# ProPrj_E73__2025-03-02.net
KiCad netlist of a schematic drawn in EasyEDA Pro
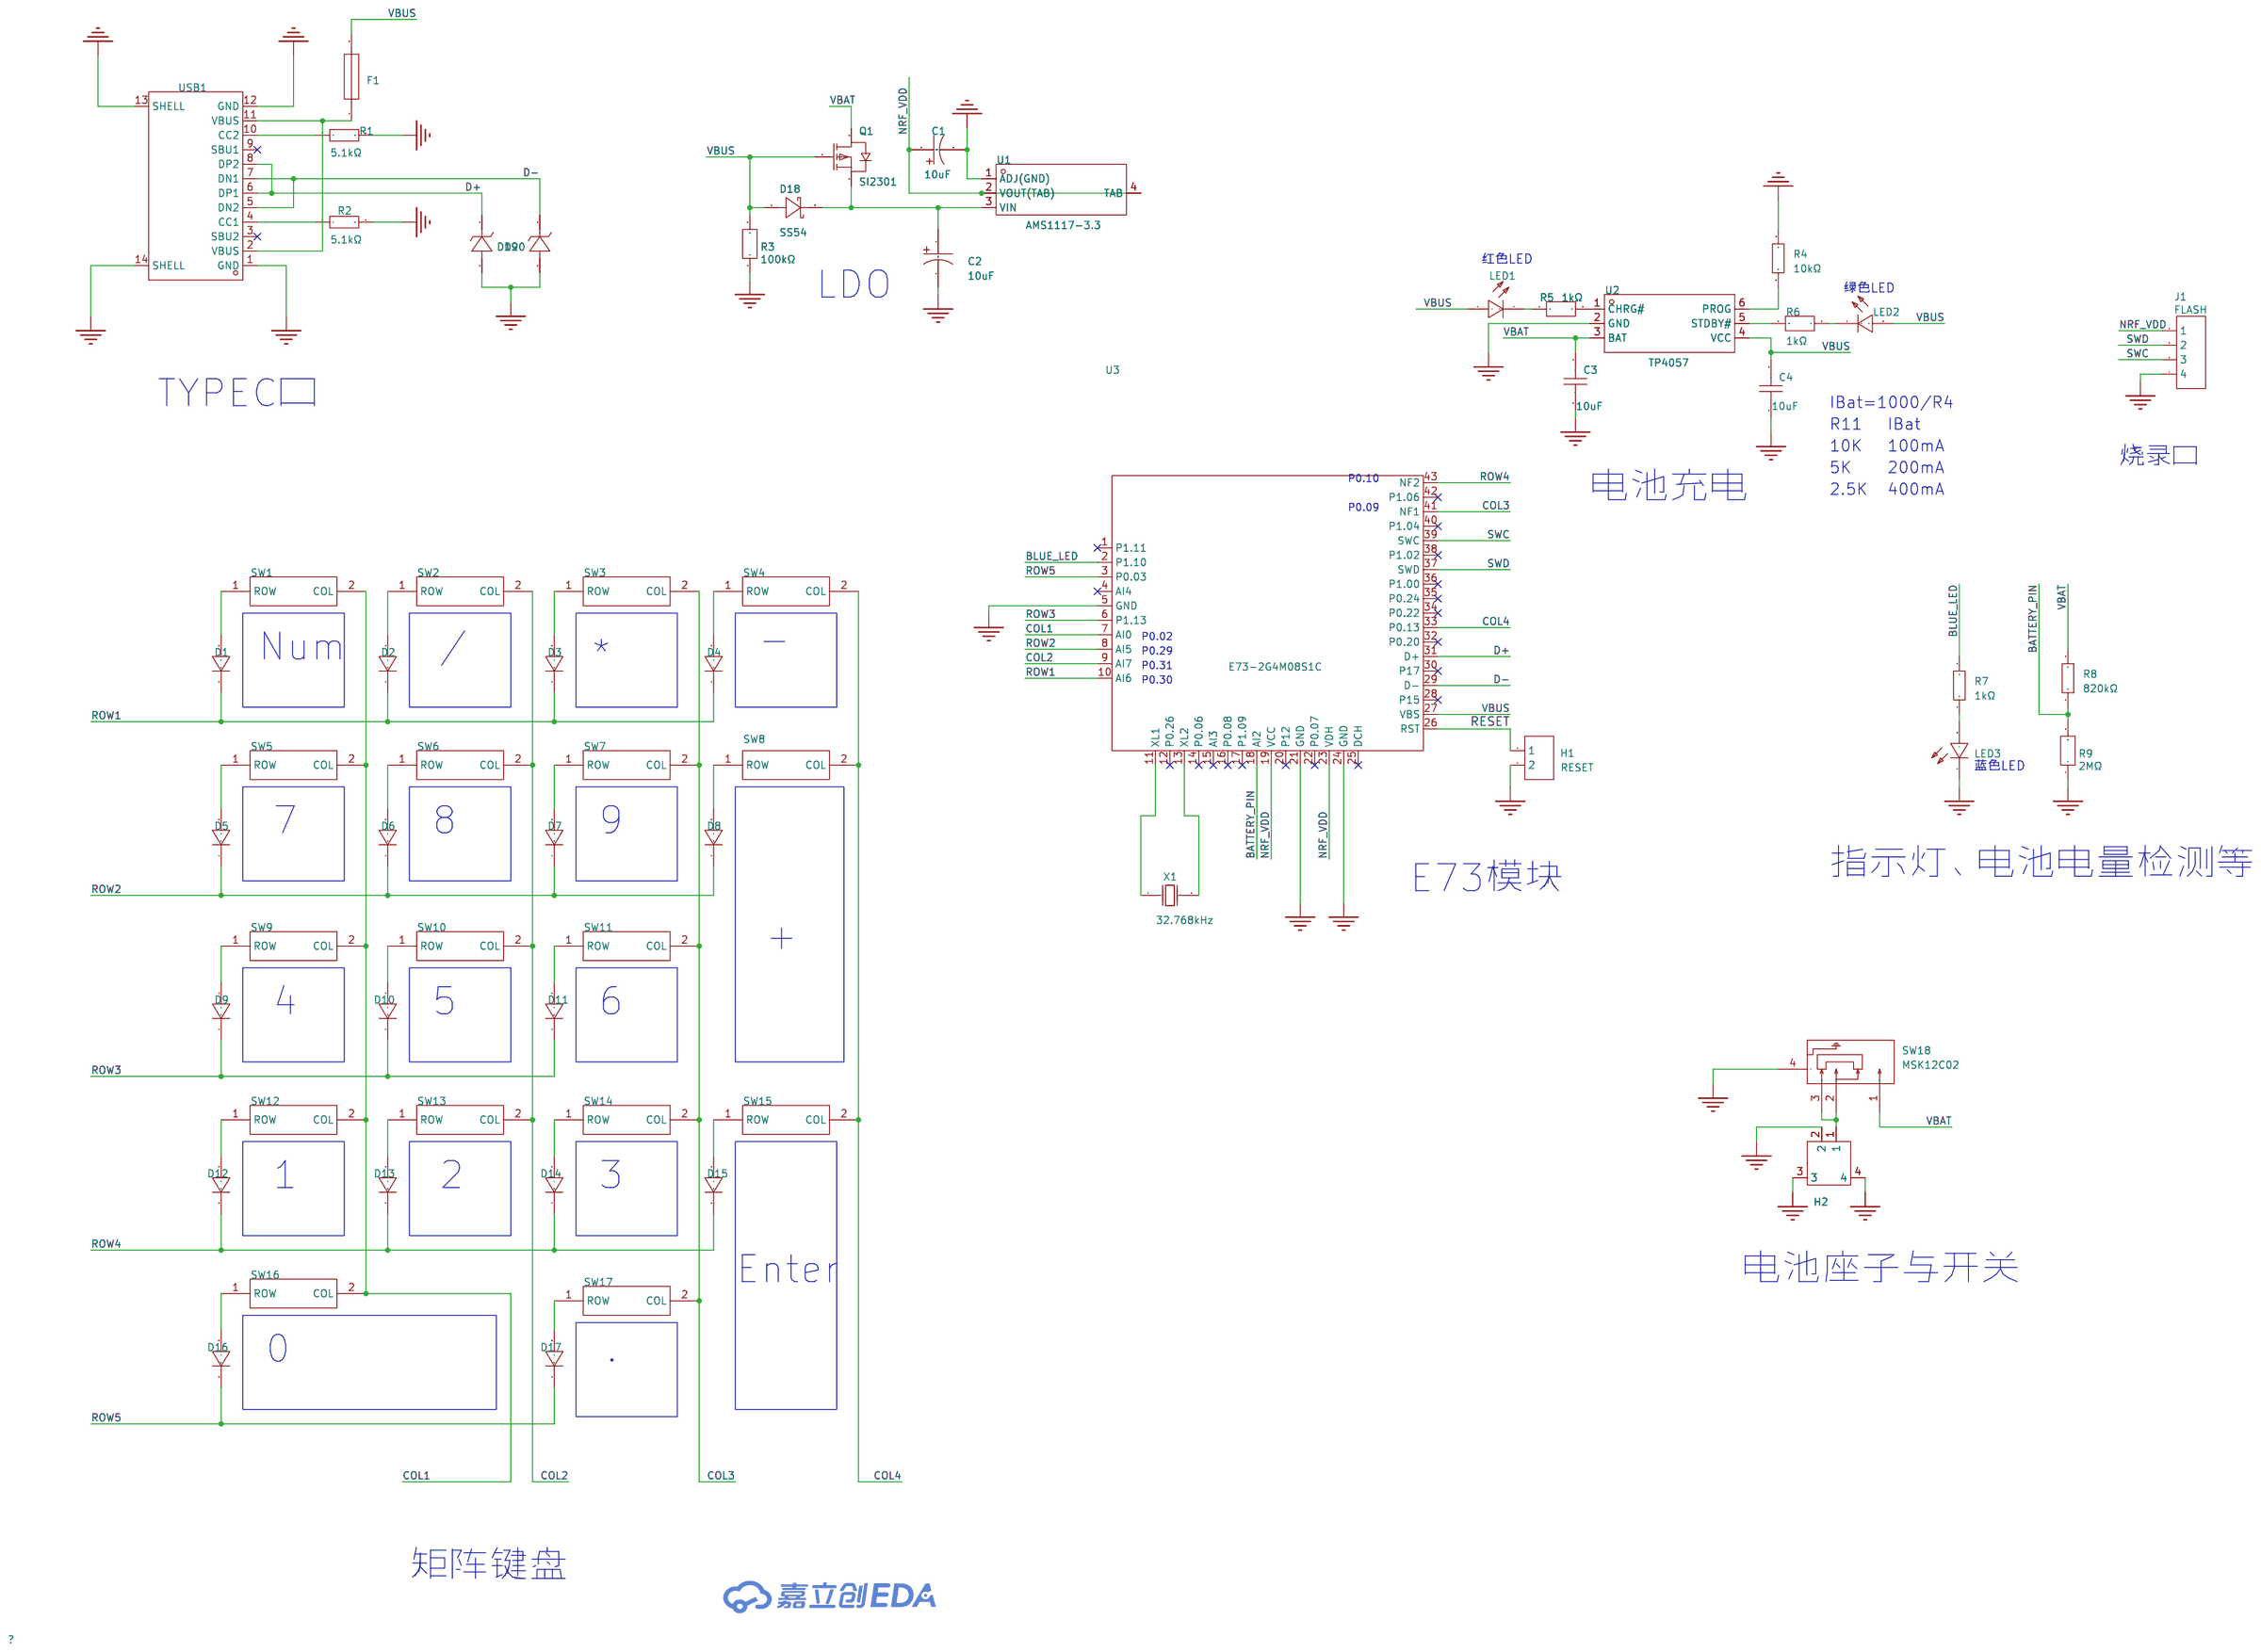
[diagram p0: schematic sheet]

(export (version "E")
  (design (tool "Eeschema 10.0.6"))
  (components
    (comp (ref "C1")
      (value "10uF")
      (footprint "easyedapro:CAP-SMD_L3.2-W1.6")
      (description "容值:10uF;精度:±10%;额定电压:16V;等效串联电阻:2Ω@100kHz;")
      (fields
        (field (name "Manufacturer Part") "CA45-A-16V-10μF-K")
        (field (name "Manufacturer") "TORCH(火炬)")
      )
      (libsource (lib "easyedapro") (part "CA45-A-16V-10μF-K"))
    )
    (comp (ref "C2")
      (value "10uF")
      (footprint "easyedapro:CAP-SMD_L3.2-W1.6")
      (description "容值:10uF;精度:±10%;额定电压:16V;等效串联电阻:2Ω@100kHz;")
      (fields
        (field (name "Manufacturer Part") "CA45-A-16V-10μF-K")
        (field (name "Manufacturer") "TORCH(火炬)")
      )
      (libsource (lib "easyedapro") (part "CA45-A-16V-10μF-K"))
    )
    (comp (ref "C3")
      (value "10uF")
      (footprint "easyedapro:C0603")
      (description "容值:10uF;精度:±20%;额定电压:16V;材质(温度系数):X5R;")
      (fields
        (field (name "Manufacturer Part") "HGC0603R5106M160NTHJ")
        (field (name "Manufacturer") "Chinocera(华瓷)")
      )
      (libsource (lib "easyedapro") (part "HGC0603R5106M160NTHJ"))
    )
    (comp (ref "C4")
      (value "10uF")
      (footprint "easyedapro:C0603")
      (description "容值:10uF;精度:±20%;额定电压:16V;材质(温度系数):X5R;")
      (fields
        (field (name "Manufacturer Part") "HGC0603R5106M160NTHJ")
        (field (name "Manufacturer") "Chinocera(华瓷)")
      )
      (libsource (lib "easyedapro") (part "HGC0603R5106M160NTHJ"))
    )
    (comp (ref "D1")
      (value "LL4148")
      (footprint "easyedapro:LL-34_L3.5-W1.5-RD")
      (description "二极管配置:-;正向压降(Vf):1V@10mA;直流反向耐压(Vr):75V;整流电流:200mA;反向恢复时间(trr):4ns;")
      (fields (field (name "Manufacturer") "MDD(辰达半导体)"))
      (libsource (lib "easyedapro") (part "LL4148_C435829"))
    )
    (comp (ref "D2")
      (value "LL4148")
      (footprint "easyedapro:LL-34_L3.5-W1.5-RD")
      (description "二极管配置:-;正向压降(Vf):1V@10mA;直流反向耐压(Vr):75V;整流电流:200mA;反向恢复时间(trr):4ns;")
      (fields (field (name "Manufacturer") "MDD(辰达半导体)"))
      (libsource (lib "easyedapro") (part "LL4148_C435829"))
    )
    (comp (ref "D3")
      (value "LL4148")
      (footprint "easyedapro:LL-34_L3.5-W1.5-RD")
      (description "二极管配置:-;正向压降(Vf):1V@10mA;直流反向耐压(Vr):75V;整流电流:200mA;反向恢复时间(trr):4ns;")
      (fields (field (name "Manufacturer") "MDD(辰达半导体)"))
      (libsource (lib "easyedapro") (part "LL4148_C435829"))
    )
    (comp (ref "D4")
      (value "LL4148")
      (footprint "easyedapro:LL-34_L3.5-W1.5-RD")
      (description "二极管配置:-;正向压降(Vf):1V@10mA;直流反向耐压(Vr):75V;整流电流:200mA;反向恢复时间(trr):4ns;")
      (fields (field (name "Manufacturer") "MDD(辰达半导体)"))
      (libsource (lib "easyedapro") (part "LL4148_C435829"))
    )
    (comp (ref "D5")
      (value "LL4148")
      (footprint "easyedapro:LL-34_L3.5-W1.5-RD")
      (description "二极管配置:-;正向压降(Vf):1V@10mA;直流反向耐压(Vr):75V;整流电流:200mA;反向恢复时间(trr):4ns;")
      (fields (field (name "Manufacturer") "MDD(辰达半导体)"))
      (libsource (lib "easyedapro") (part "LL4148_C435829"))
    )
    (comp (ref "D6")
      (value "LL4148")
      (footprint "easyedapro:LL-34_L3.5-W1.5-RD")
      (description "二极管配置:-;正向压降(Vf):1V@10mA;直流反向耐压(Vr):75V;整流电流:200mA;反向恢复时间(trr):4ns;")
      (fields (field (name "Manufacturer") "MDD(辰达半导体)"))
      (libsource (lib "easyedapro") (part "LL4148_C435829"))
    )
    (comp (ref "D7")
      (value "LL4148")
      (footprint "easyedapro:LL-34_L3.5-W1.5-RD")
      (description "二极管配置:-;正向压降(Vf):1V@10mA;直流反向耐压(Vr):75V;整流电流:200mA;反向恢复时间(trr):4ns;")
      (fields (field (name "Manufacturer") "MDD(辰达半导体)"))
      (libsource (lib "easyedapro") (part "LL4148_C435829"))
    )
    (comp (ref "D8")
      (value "LL4148")
      (footprint "easyedapro:LL-34_L3.5-W1.5-RD")
      (description "二极管配置:-;正向压降(Vf):1V@10mA;直流反向耐压(Vr):75V;整流电流:200mA;反向恢复时间(trr):4ns;")
      (fields (field (name "Manufacturer") "MDD(辰达半导体)"))
      (libsource (lib "easyedapro") (part "LL4148_C435829"))
    )
    (comp (ref "D9")
      (value "LL4148")
      (footprint "easyedapro:LL-34_L3.5-W1.5-RD")
      (description "二极管配置:-;正向压降(Vf):1V@10mA;直流反向耐压(Vr):75V;整流电流:200mA;反向恢复时间(trr):4ns;")
      (fields (field (name "Manufacturer") "MDD(辰达半导体)"))
      (libsource (lib "easyedapro") (part "LL4148_C435829"))
    )
    (comp (ref "D10")
      (value "LL4148")
      (footprint "easyedapro:LL-34_L3.5-W1.5-RD")
      (description "二极管配置:-;正向压降(Vf):1V@10mA;直流反向耐压(Vr):75V;整流电流:200mA;反向恢复时间(trr):4ns;")
      (fields (field (name "Manufacturer") "MDD(辰达半导体)"))
      (libsource (lib "easyedapro") (part "LL4148_C435829"))
    )
    (comp (ref "D11")
      (value "LL4148")
      (footprint "easyedapro:LL-34_L3.5-W1.5-RD")
      (description "二极管配置:-;正向压降(Vf):1V@10mA;直流反向耐压(Vr):75V;整流电流:200mA;反向恢复时间(trr):4ns;")
      (fields (field (name "Manufacturer") "MDD(辰达半导体)"))
      (libsource (lib "easyedapro") (part "LL4148_C435829"))
    )
    (comp (ref "D12")
      (value "LL4148")
      (footprint "easyedapro:LL-34_L3.5-W1.5-RD")
      (description "二极管配置:-;正向压降(Vf):1V@10mA;直流反向耐压(Vr):75V;整流电流:200mA;反向恢复时间(trr):4ns;")
      (fields (field (name "Manufacturer") "MDD(辰达半导体)"))
      (libsource (lib "easyedapro") (part "LL4148_C435829"))
    )
    (comp (ref "D13")
      (value "LL4148")
      (footprint "easyedapro:LL-34_L3.5-W1.5-RD")
      (description "二极管配置:-;正向压降(Vf):1V@10mA;直流反向耐压(Vr):75V;整流电流:200mA;反向恢复时间(trr):4ns;")
      (fields (field (name "Manufacturer") "MDD(辰达半导体)"))
      (libsource (lib "easyedapro") (part "LL4148_C435829"))
    )
    (comp (ref "D14")
      (value "LL4148")
      (footprint "easyedapro:LL-34_L3.5-W1.5-RD")
      (description "二极管配置:-;正向压降(Vf):1V@10mA;直流反向耐压(Vr):75V;整流电流:200mA;反向恢复时间(trr):4ns;")
      (fields (field (name "Manufacturer") "MDD(辰达半导体)"))
      (libsource (lib "easyedapro") (part "LL4148_C435829"))
    )
    (comp (ref "D15")
      (value "LL4148")
      (footprint "easyedapro:LL-34_L3.5-W1.5-RD")
      (description "二极管配置:-;正向压降(Vf):1V@10mA;直流反向耐压(Vr):75V;整流电流:200mA;反向恢复时间(trr):4ns;")
      (fields (field (name "Manufacturer") "MDD(辰达半导体)"))
      (libsource (lib "easyedapro") (part "LL4148_C435829"))
    )
    (comp (ref "D16")
      (value "LL4148")
      (footprint "easyedapro:LL-34_L3.5-W1.5-RD")
      (description "二极管配置:-;正向压降(Vf):1V@10mA;直流反向耐压(Vr):75V;整流电流:200mA;反向恢复时间(trr):4ns;")
      (fields (field (name "Manufacturer") "MDD(辰达半导体)"))
      (libsource (lib "easyedapro") (part "LL4148_C435829"))
    )
    (comp (ref "D17")
      (value "LL4148")
      (footprint "easyedapro:LL-34_L3.5-W1.5-RD")
      (description "二极管配置:-;正向压降(Vf):1V@10mA;直流反向耐压(Vr):75V;整流电流:200mA;反向恢复时间(trr):4ns;")
      (fields (field (name "Manufacturer") "MDD(辰达半导体)"))
      (libsource (lib "easyedapro") (part "LL4148_C435829"))
    )
    (comp (ref "D18")
      (value "SS54")
      (footprint "easyedapro:SMA_L4.3-W2.6-LS5.0-FD")
      (description "二极管配置:独立式;正向压降(Vf):550mV@5.0A;直流反向耐压(Vr):40V;整流电流:5A;")
      (fields (field (name "Manufacturer") "宏迦橙"))
      (libsource (lib "easyedapro") (part "SS54_C7420369"))
    )
    (comp (ref "D19")
      (value "BZT52C3V6S")
      (footprint "easyedapro:SOD-323_L1.7-W1.3-LS2.6-RD")
      (description "二极管配置:独立式;稳压值(标称值):3.6V;稳压值(范围):3.4V~3.8V;功率(Pd):200mW;")
      (fields (field (name "Manufacturer") "宏迦橙"))
      (libsource (lib "easyedapro") (part "BZT52C3V6S_C19077438"))
    )
    (comp (ref "D20")
      (value "BZT52C3V6S")
      (footprint "easyedapro:SOD-323_L1.7-W1.3-LS2.6-RD")
      (description "二极管配置:独立式;稳压值(标称值):3.6V;稳压值(范围):3.4V~3.8V;功率(Pd):200mW;")
      (fields (field (name "Manufacturer") "宏迦橙"))
      (libsource (lib "easyedapro") (part "BZT52C3V6S_C19077438"))
    )
    (comp (ref "F1")
      (value "JK-nSMD050-30")
      (footprint "easyedapro:F1206")
      (description "最大电压:30V;最大电流:100A;保持电流:500mA;跳闸电流:1A;")
      (fields (field (name "Manufacturer") "JK(金科)"))
      (libsource (lib "easyedapro") (part "JK-NSMD050-30V"))
    )
    (comp (ref "H1")
      (value "RESET")
      (footprint "easyedapro:PIN02")
      (libsource (lib "easyedapro") (part "RESET"))
    )
    (comp (ref "H2") (value "2.54-2P WT") (libsource (lib "easyedapro") (part "Battery")))
    (comp (ref "J1")
      (value "FLASH")
      (footprint "easyedapro:PIN04")
      (libsource (lib "easyedapro") (part "FLASH"))
    )
    (comp (ref "LED1")
      (value "NCD0603R1")
      (footprint "easyedapro:LED0603-RD_RED")
      (fields (field (name "Manufacturer") "国星光电"))
      (libsource (lib "easyedapro") (part "FC-DA1608HRK-620D"))
    )
    (comp (ref "LED2")
      (value "NCD0603G1")
      (footprint "easyedapro:LED0603-RD_1")
      (fields (field (name "Manufacturer") "国星光电"))
      (libsource (lib "easyedapro") (part "FC-D1608UGK-520D10"))
    )
    (comp (ref "LED3")
      (value "NCD0603B1")
      (footprint "easyedapro:LED0603-RD")
      (fields (field (name "Manufacturer") "国星光电"))
      (libsource (lib "easyedapro") (part "FC-DA1608BK-470H10"))
    )
    (comp (ref "Q1")
      (value "SI2301")
      (footprint "easyedapro:SOT-23-3_L2.9-W1.3-P1.90-LS2.4-BR")
      (fields (field (name "Manufacturer") "YONGYUTAI(永裕泰)"))
      (libsource (lib "easyedapro") (part "SI2301_C2891731"))
    )
    (comp (ref "R1")
      (value "5.1kΩ")
      (footprint "easyedapro:R0603")
      (description "电阻类型:厚膜电阻;阻值:5.1kΩ;精度:±1%;功率:100mW;最大工作电压:75V;温度系数:±100ppm/°C;")
      (fields
        (field (name "Manufacturer Part") "0603WAF5101T5E")
        (field (name "Manufacturer") "UNI-ROYAL(厚声)")
      )
      (libsource (lib "easyedapro") (part "0603WAF5101T5E"))
    )
    (comp (ref "R2")
      (value "5.1kΩ")
      (footprint "easyedapro:R0603")
      (description "电阻类型:厚膜电阻;阻值:5.1kΩ;精度:±1%;功率:100mW;最大工作电压:75V;温度系数:±100ppm/°C;")
      (fields
        (field (name "Manufacturer Part") "0603WAF5101T5E")
        (field (name "Manufacturer") "UNI-ROYAL(厚声)")
      )
      (libsource (lib "easyedapro") (part "0603WAF5101T5E"))
    )
    (comp (ref "R3")
      (value "100kΩ")
      (fields (field (name "Manufacturer") "UNI-ROYAL(厚声)"))
      (libsource (lib "easyedapro") (part "100K"))
    )
    (comp (ref "R4")
      (value "10kΩ")
      (footprint "easyedapro:R0603")
      (description "电阻类型:厚膜电阻;阻值:10kΩ;精度:±1%;功率:100mW;最大工作电压:75V;温度系数:±100ppm/°C;")
      (fields
        (field (name "Manufacturer Part") "0603WAF1002T5E")
        (field (name "Manufacturer") "UNI-ROYAL(厚声)")
      )
      (libsource (lib "easyedapro") (part "0603WAF1002T5E"))
    )
    (comp (ref "R5")
      (value "1kΩ")
      (fields (field (name "Manufacturer") "UNI-ROYAL(厚声)"))
      (libsource (lib "easyedapro") (part "1K"))
    )
    (comp (ref "R6")
      (value "1kΩ")
      (fields (field (name "Manufacturer") "UNI-ROYAL(厚声)"))
      (libsource (lib "easyedapro") (part "1K"))
    )
    (comp (ref "R7")
      (value "1kΩ")
      (footprint "easyedapro:R0603")
      (description "电阻类型:厚膜电阻;阻值:1kΩ;精度:±1%;功率:100mW;最大工作电压:75V;温度系数:±100ppm/°C;")
      (fields
        (field (name "Manufacturer Part") "0603WAF1001T5E")
        (field (name "Manufacturer") "UNI-ROYAL(厚声)")
      )
      (libsource (lib "easyedapro") (part "0603WAF1001T5E"))
    )
    (comp (ref "R8")
      (value "820kΩ")
      (footprint "easyedapro:R0603")
      (description "电阻类型:厚膜电阻;阻值:820kΩ;精度:±1%;功率:100mW;最大工作电压:75V;温度系数:±100ppm/°C;")
      (fields
        (field (name "Manufacturer Part") "0603WAF8203T5E")
        (field (name "Manufacturer") "UNI-ROYAL(厚声)")
      )
      (libsource (lib "easyedapro") (part "0603WAF8203T5E"))
    )
    (comp (ref "R9")
      (value "2MΩ")
      (fields (field (name "Manufacturer") "UNI-ROYAL(厚声)"))
      (libsource (lib "easyedapro") (part "2M"))
    )
    (comp (ref "SW1")
      (value "~")
      (footprint "easyedapro:键盘轴座(无灯)")
      (libsource (lib "easyedapro") (part "键盘轴座(无灯)"))
    )
    (comp (ref "SW2")
      (value "~")
      (footprint "easyedapro:键盘轴座(无灯)")
      (libsource (lib "easyedapro") (part "键盘轴座(无灯)"))
    )
    (comp (ref "SW3")
      (value "~")
      (footprint "easyedapro:键盘轴座(无灯)")
      (libsource (lib "easyedapro") (part "键盘轴座(无灯)"))
    )
    (comp (ref "SW4")
      (value "~")
      (footprint "easyedapro:键盘轴座(无灯)")
      (libsource (lib "easyedapro") (part "键盘轴座(无灯)"))
    )
    (comp (ref "SW5")
      (value "~")
      (footprint "easyedapro:键盘轴座(无灯)")
      (libsource (lib "easyedapro") (part "键盘轴座(无灯)"))
    )
    (comp (ref "SW6")
      (value "~")
      (footprint "easyedapro:键盘轴座(无灯)")
      (libsource (lib "easyedapro") (part "键盘轴座(无灯)"))
    )
    (comp (ref "SW7")
      (value "~")
      (footprint "easyedapro:键盘轴座(无灯)")
      (libsource (lib "easyedapro") (part "键盘轴座(无灯)"))
    )
    (comp (ref "SW8")
      (value "~")
      (footprint "easyedapro:键盘轴座(无灯)")
      (libsource (lib "easyedapro") (part "键盘轴座(无灯)"))
    )
    (comp (ref "SW9")
      (value "~")
      (footprint "easyedapro:键盘轴座(无灯)")
      (libsource (lib "easyedapro") (part "键盘轴座(无灯)"))
    )
    (comp (ref "SW10")
      (value "~")
      (footprint "easyedapro:键盘轴座(无灯)")
      (libsource (lib "easyedapro") (part "键盘轴座(无灯)"))
    )
    (comp (ref "SW11")
      (value "~")
      (footprint "easyedapro:键盘轴座(无灯)")
      (libsource (lib "easyedapro") (part "键盘轴座(无灯)"))
    )
    (comp (ref "SW12")
      (value "~")
      (footprint "easyedapro:键盘轴座(无灯)")
      (libsource (lib "easyedapro") (part "键盘轴座(无灯)"))
    )
    (comp (ref "SW13")
      (value "~")
      (footprint "easyedapro:键盘轴座(无灯)")
      (libsource (lib "easyedapro") (part "键盘轴座(无灯)"))
    )
    (comp (ref "SW14")
      (value "~")
      (footprint "easyedapro:键盘轴座(无灯)")
      (libsource (lib "easyedapro") (part "键盘轴座(无灯)"))
    )
    (comp (ref "SW15")
      (value "~")
      (footprint "easyedapro:键盘轴座(无灯)")
      (libsource (lib "easyedapro") (part "键盘轴座(无灯)"))
    )
    (comp (ref "SW16")
      (value "~")
      (footprint "easyedapro:键盘轴座(无灯)")
      (libsource (lib "easyedapro") (part "键盘轴座(无灯)"))
    )
    (comp (ref "SW17")
      (value "~")
      (footprint "easyedapro:键盘轴座(无灯)")
      (libsource (lib "easyedapro") (part "键盘轴座(无灯)"))
    )
    (comp (ref "SW18")
      (value "MSK12C02")
      (footprint "easyedapro:SW-TH_MSK12C02")
      (description "电路结构:单刀双掷;安装方式:卧贴;开关颜色:-;额定电流(DC):50mA;额定电压(DC):12V;额定电流(AC):-;额定电压(AC):-;机械寿命:1万次;")
      (fields (field (name "Manufacturer") "SHOU HAN(首韩)"))
      (libsource (lib "easyedapro") (part "MSK12C02"))
    )
    (comp (ref "U1")
      (value "AMS1117-3.3")
      (footprint "easyedapro:SOT-223-4_L6.5-W3.5-P2.30-LS7.0-BR")
      (description "输出类型:固定;工作电压:12V;输出电压:3.3V;输出电流:1A;电源纹波抑制比(PSRR):60dB@(120Hz);输出极性:正极;")
      (fields (field (name "Manufacturer") "UMW(友台半导体)"))
      (libsource (lib "easyedapro") (part "AMS1117-3.3_C347222"))
    )
    (comp (ref "U2")
      (value "TP4057")
      (footprint "easyedapro:SOT-23-6_L2.9-W1.6-P0.95-LS2.8-BR")
      (description "电源电压:6.5V;最大充电电流:500mA;电池类型:锂离子/聚合物;电池节数:1;")
      (fields (field (name "Manufacturer") "UMW(友台半导体)"))
      (libsource (lib "easyedapro") (part "TP4057_C725791"))
    )
    (comp (ref "U3")
      (value "E73-2G4M08S1C")
      (footprint "easyedapro:WIRELM-SMD_E73-2G4M08S1C")
      (fields (field (name "Manufacturer") "EBYTE(亿佰特)"))
      (libsource (lib "easyedapro") (part "E73-2G4M08S1C"))
    )
    (comp (ref "USB1")
      (value "TYPE-C 16PIN 2MD(073)")
      (footprint "easyedapro:USB-C-SMD_TYPE-C-6PIN-2MD-073")
      (description "连接器类型:Type-C;标准:USB 3.1;公母:母;安装方式:卧贴;触点数量:16P;端口数量:1;额定电流 - 电源:5A;工作温度范围:-25°C~+85°C;")
      (fields (field (name "Manufacturer") "SHOU HAN(首韩)"))
      (libsource (lib "easyedapro") (part "TYPE-C 16PIN 2MD(073)"))
    )
    (comp (ref "X1")
      (value "32.768kHz")
      (footprint "easyedapro:CRYSTAL-SMD_L3.2-W1.5-1")
      (description "晶振类型:贴片晶振;频率:32.768kHz;常温频差:±20ppm;负载电容:12.5pF;频率稳定度:±30ppm;")
      (fields
        (field (name "Manufacturer Part") "XKXGI-SUA-32.768K")
        (field (name "Manufacturer") "YXC(扬兴晶振)")
      )
      (libsource (lib "easyedapro") (part "XKXGI-SUA-32.768K"))
    )
  )
  (nets
    (net (code "1") (name "/BATTERY_PIN") (class "Default")
      (node (ref "R8") (pin "1") (pinfunction "1_1") (pintype "input"))
      (node (ref "R9") (pin "2") (pinfunction "2_2") (pintype "unspecified"))
      (node (ref "U3") (pin "18") (pinfunction "AI2_18") (pintype "unspecified"))
    )
    (net (code "2") (name "/BLUE_LED") (class "Default")
      (node (ref "R7") (pin "2") (pinfunction "2_2") (pintype "input"))
      (node (ref "U3") (pin "2") (pinfunction "P1.10_2") (pintype "unspecified"))
    )
    (net (code "3") (name "/COL1") (class "Default")
      (node (ref "SW1") (pin "2") (pinfunction "COL_2") (pintype "input"))
      (node (ref "SW12") (pin "2") (pinfunction "COL_2") (pintype "input"))
      (node (ref "SW16") (pin "2") (pinfunction "COL_2") (pintype "input"))
      (node (ref "SW5") (pin "2") (pinfunction "COL_2") (pintype "input"))
      (node (ref "SW9") (pin "2") (pinfunction "COL_2") (pintype "input"))
      (node (ref "U3") (pin "7") (pinfunction "AI0_7") (pintype "unspecified"))
    )
    (net (code "4") (name "/COL2") (class "Default")
      (node (ref "SW10") (pin "2") (pinfunction "COL_2") (pintype "input"))
      (node (ref "SW13") (pin "2") (pinfunction "COL_2") (pintype "input"))
      (node (ref "SW2") (pin "2") (pinfunction "COL_2") (pintype "input"))
      (node (ref "SW6") (pin "2") (pinfunction "COL_2") (pintype "input"))
      (node (ref "U3") (pin "9") (pinfunction "AI7_9") (pintype "unspecified"))
    )
    (net (code "5") (name "/COL3") (class "Default")
      (node (ref "SW11") (pin "2") (pinfunction "COL_2") (pintype "input"))
      (node (ref "SW14") (pin "2") (pinfunction "COL_2") (pintype "input"))
      (node (ref "SW17") (pin "2") (pinfunction "COL_2") (pintype "input"))
      (node (ref "SW3") (pin "2") (pinfunction "COL_2") (pintype "input"))
      (node (ref "SW7") (pin "2") (pinfunction "COL_2") (pintype "input"))
      (node (ref "U3") (pin "41") (pinfunction "NF1_41") (pintype "unspecified"))
    )
    (net (code "6") (name "/COL4") (class "Default")
      (node (ref "SW15") (pin "2") (pinfunction "COL_2") (pintype "input"))
      (node (ref "SW4") (pin "2") (pinfunction "COL_2") (pintype "input"))
      (node (ref "SW8") (pin "2") (pinfunction "COL_2") (pintype "input"))
      (node (ref "U3") (pin "33") (pinfunction "P0.13_33") (pintype "unspecified"))
    )
    (net (code "7") (name "/D+") (class "Default")
      (node (ref "D19") (pin "1") (pinfunction "K_1") (pintype "unspecified"))
      (node (ref "U3") (pin "31") (pinfunction "D+_31") (pintype "unspecified"))
      (node (ref "USB1") (pin "6") (pinfunction "DP1_6") (pintype "unspecified"))
      (node (ref "USB1") (pin "8") (pinfunction "DP2_8") (pintype "unspecified"))
    )
    (net (code "8") (name "/D-") (class "Default")
      (node (ref "D20") (pin "1") (pinfunction "K_1") (pintype "unspecified"))
      (node (ref "U3") (pin "29") (pinfunction "D-_29") (pintype "unspecified"))
      (node (ref "USB1") (pin "5") (pinfunction "DN2_5") (pintype "unspecified"))
      (node (ref "USB1") (pin "7") (pinfunction "DN1_7") (pintype "unspecified"))
    )
    (net (code "9") (name "/NRF_VDD") (class "Default")
      (node (ref "C1") (pin "1") (pinfunction "1_1") (pintype "unspecified"))
      (node (ref "J1") (pin "1") (pinfunction "1_1") (pintype "unspecified"))
      (node (ref "U1") (pin "2") (pinfunction "VOUT(TAB)_2") (pintype "unspecified"))
      (node (ref "U1") (pin "4") (pinfunction "TAB_4") (pintype "unspecified"))
      (node (ref "U3") (pin "19") (pinfunction "VCC_19") (pintype "unspecified"))
      (node (ref "U3") (pin "23") (pinfunction "VDH_23") (pintype "unspecified"))
    )
    (net (code "10") (name "/RESET") (class "Default")
      (node (ref "H1") (pin "1") (pinfunction "1_1") (pintype "input"))
      (node (ref "U3") (pin "26") (pinfunction "RST_26") (pintype "unspecified"))
    )
    (net (code "11") (name "/ROW1") (class "Default")
      (node (ref "D1") (pin "1") (pinfunction "C_1") (pintype "unspecified"))
      (node (ref "D2") (pin "1") (pinfunction "C_1") (pintype "unspecified"))
      (node (ref "D3") (pin "1") (pinfunction "C_1") (pintype "unspecified"))
      (node (ref "D4") (pin "1") (pinfunction "C_1") (pintype "unspecified"))
      (node (ref "U3") (pin "10") (pinfunction "AI6_10") (pintype "unspecified"))
    )
    (net (code "12") (name "/ROW2") (class "Default")
      (node (ref "D5") (pin "1") (pinfunction "C_1") (pintype "unspecified"))
      (node (ref "D6") (pin "1") (pinfunction "C_1") (pintype "unspecified"))
      (node (ref "D7") (pin "1") (pinfunction "C_1") (pintype "unspecified"))
      (node (ref "D8") (pin "1") (pinfunction "C_1") (pintype "unspecified"))
      (node (ref "U3") (pin "8") (pinfunction "AI5_8") (pintype "unspecified"))
    )
    (net (code "13") (name "/ROW3") (class "Default")
      (node (ref "D10") (pin "1") (pinfunction "C_1") (pintype "unspecified"))
      (node (ref "D11") (pin "1") (pinfunction "C_1") (pintype "unspecified"))
      (node (ref "D9") (pin "1") (pinfunction "C_1") (pintype "unspecified"))
      (node (ref "U3") (pin "6") (pinfunction "P1.13_6") (pintype "unspecified"))
    )
    (net (code "14") (name "/ROW4") (class "Default")
      (node (ref "D12") (pin "1") (pinfunction "C_1") (pintype "unspecified"))
      (node (ref "D13") (pin "1") (pinfunction "C_1") (pintype "unspecified"))
      (node (ref "D14") (pin "1") (pinfunction "C_1") (pintype "unspecified"))
      (node (ref "D15") (pin "1") (pinfunction "C_1") (pintype "unspecified"))
      (node (ref "U3") (pin "43") (pinfunction "NF2_43") (pintype "unspecified"))
    )
    (net (code "15") (name "/ROW5") (class "Default")
      (node (ref "D16") (pin "1") (pinfunction "C_1") (pintype "unspecified"))
      (node (ref "D17") (pin "1") (pinfunction "C_1") (pintype "unspecified"))
      (node (ref "U3") (pin "3") (pinfunction "P0.03_3") (pintype "unspecified"))
    )
    (net (code "16") (name "/SWC") (class "Default")
      (node (ref "J1") (pin "3") (pinfunction "3_3") (pintype "unspecified"))
      (node (ref "U3") (pin "39") (pinfunction "SWC_39") (pintype "unspecified"))
    )
    (net (code "17") (name "/SWD") (class "Default")
      (node (ref "J1") (pin "2") (pinfunction "2_2") (pintype "unspecified"))
      (node (ref "U3") (pin "37") (pinfunction "SWD_37") (pintype "unspecified"))
    )
    (net (code "18") (name "/VBAT") (class "Default")
      (node (ref "C3") (pin "1") (pinfunction "1_1") (pintype "unspecified"))
      (node (ref "Q1") (pin "3") (pinfunction "D_3") (pintype "unspecified"))
      (node (ref "R8") (pin "2") (pinfunction "2_2") (pintype "input"))
      (node (ref "SW18") (pin "1") (pinfunction "1_1") (pintype "unspecified"))
      (node (ref "U2") (pin "3") (pinfunction "BAT_3") (pintype "unspecified"))
    )
    (net (code "19") (name "/VBUS") (class "Default")
      (node (ref "C4") (pin "2") (pinfunction "2_2") (pintype "unspecified"))
      (node (ref "D18") (pin "1") (pinfunction "A_1") (pintype "unspecified"))
      (node (ref "F1") (pin "2") (pinfunction "2_2") (pintype "unspecified"))
      (node (ref "LED1") (pin "2") (pinfunction "A_2") (pintype "input"))
      (node (ref "LED2") (pin "2") (pinfunction "A_2") (pintype "input"))
      (node (ref "Q1") (pin "1") (pinfunction "G_1") (pintype "unspecified"))
      (node (ref "R3") (pin "2") (pinfunction "2_2") (pintype "unspecified"))
      (node (ref "U2") (pin "4") (pinfunction "VCC_4") (pintype "unspecified"))
      (node (ref "U3") (pin "27") (pinfunction "VBS_27") (pintype "unspecified"))
    )
    (net (code "20") (name "GND") (class "Default")
      (node (ref "C1") (pin "2") (pinfunction "2_2") (pintype "unspecified"))
      (node (ref "C2") (pin "2") (pinfunction "2_2") (pintype "unspecified"))
      (node (ref "C3") (pin "2") (pinfunction "2_2") (pintype "unspecified"))
      (node (ref "C4") (pin "1") (pinfunction "1_1") (pintype "unspecified"))
      (node (ref "D19") (pin "2") (pinfunction "A_2") (pintype "unspecified"))
      (node (ref "D20") (pin "2") (pinfunction "A_2") (pintype "unspecified"))
      (node (ref "H1") (pin "2") (pinfunction "2_2") (pintype "input"))
      (node (ref "H2") (pin "2") (pinfunction "2_2") (pintype "unspecified"))
      (node (ref "H2") (pin "3") (pinfunction "3_3") (pintype "unspecified"))
      (node (ref "H2") (pin "4") (pinfunction "4_4") (pintype "unspecified"))
      (node (ref "J1") (pin "4") (pinfunction "4_4") (pintype "unspecified"))
      (node (ref "LED3") (pin "1") (pinfunction "-_1") (pintype "input"))
      (node (ref "R1") (pin "2") (pinfunction "2_2") (pintype "input"))
      (node (ref "R2") (pin "2") (pinfunction "2_2") (pintype "input"))
      (node (ref "R3") (pin "1") (pinfunction "1_1") (pintype "unspecified"))
      (node (ref "R4") (pin "2") (pinfunction "2_2") (pintype "input"))
      (node (ref "R9") (pin "1") (pinfunction "1_1") (pintype "unspecified"))
      (node (ref "SW18") (pin "4") (pinfunction "4_4") (pintype "unspecified"))
      (node (ref "U1") (pin "1") (pinfunction "ADJ(GND)_1") (pintype "unspecified"))
      (node (ref "U2") (pin "2") (pinfunction "GND_2") (pintype "unspecified"))
      (node (ref "U3") (pin "21") (pinfunction "GND_21") (pintype "unspecified"))
      (node (ref "U3") (pin "24") (pinfunction "GND_24") (pintype "unspecified"))
      (node (ref "U3") (pin "5") (pinfunction "GND_5") (pintype "unspecified"))
      (node (ref "USB1") (pin "1") (pinfunction "GND_1") (pintype "unspecified"))
      (node (ref "USB1") (pin "12") (pinfunction "GND_12") (pintype "unspecified"))
      (node (ref "USB1") (pin "13") (pinfunction "SHELL_13") (pintype "unspecified"))
      (node (ref "USB1") (pin "14") (pinfunction "SHELL_14") (pintype "unspecified"))
    )
    (net (code "21") (name "Net-(D1-A)") (class "Default")
      (node (ref "D1") (pin "2") (pinfunction "A_2") (pintype "unspecified"))
      (node (ref "SW1") (pin "1") (pinfunction "ROW_1") (pintype "input"))
    )
    (net (code "22") (name "Net-(D2-A)") (class "Default")
      (node (ref "D2") (pin "2") (pinfunction "A_2") (pintype "unspecified"))
      (node (ref "SW2") (pin "1") (pinfunction "ROW_1") (pintype "input"))
    )
    (net (code "23") (name "Net-(D3-A)") (class "Default")
      (node (ref "D3") (pin "2") (pinfunction "A_2") (pintype "unspecified"))
      (node (ref "SW3") (pin "1") (pinfunction "ROW_1") (pintype "input"))
    )
    (net (code "24") (name "Net-(D4-A)") (class "Default")
      (node (ref "D4") (pin "2") (pinfunction "A_2") (pintype "unspecified"))
      (node (ref "SW4") (pin "1") (pinfunction "ROW_1") (pintype "input"))
    )
    (net (code "25") (name "Net-(D5-A)") (class "Default")
      (node (ref "D5") (pin "2") (pinfunction "A_2") (pintype "unspecified"))
      (node (ref "SW5") (pin "1") (pinfunction "ROW_1") (pintype "input"))
    )
    (net (code "26") (name "Net-(D6-A)") (class "Default")
      (node (ref "D6") (pin "2") (pinfunction "A_2") (pintype "unspecified"))
      (node (ref "SW6") (pin "1") (pinfunction "ROW_1") (pintype "input"))
    )
    (net (code "27") (name "Net-(D7-A)") (class "Default")
      (node (ref "D7") (pin "2") (pinfunction "A_2") (pintype "unspecified"))
      (node (ref "SW7") (pin "1") (pinfunction "ROW_1") (pintype "input"))
    )
    (net (code "28") (name "Net-(D8-A)") (class "Default")
      (node (ref "D8") (pin "2") (pinfunction "A_2") (pintype "unspecified"))
      (node (ref "SW8") (pin "1") (pinfunction "ROW_1") (pintype "input"))
    )
    (net (code "29") (name "Net-(D9-A)") (class "Default")
      (node (ref "D9") (pin "2") (pinfunction "A_2") (pintype "unspecified"))
      (node (ref "SW9") (pin "1") (pinfunction "ROW_1") (pintype "input"))
    )
    (net (code "30") (name "Net-(D10-A)") (class "Default")
      (node (ref "D10") (pin "2") (pinfunction "A_2") (pintype "unspecified"))
      (node (ref "SW10") (pin "1") (pinfunction "ROW_1") (pintype "input"))
    )
    (net (code "31") (name "Net-(D11-A)") (class "Default")
      (node (ref "D11") (pin "2") (pinfunction "A_2") (pintype "unspecified"))
      (node (ref "SW11") (pin "1") (pinfunction "ROW_1") (pintype "input"))
    )
    (net (code "32") (name "Net-(D12-A)") (class "Default")
      (node (ref "D12") (pin "2") (pinfunction "A_2") (pintype "unspecified"))
      (node (ref "SW12") (pin "1") (pinfunction "ROW_1") (pintype "input"))
    )
    (net (code "33") (name "Net-(D13-A)") (class "Default")
      (node (ref "D13") (pin "2") (pinfunction "A_2") (pintype "unspecified"))
      (node (ref "SW13") (pin "1") (pinfunction "ROW_1") (pintype "input"))
    )
    (net (code "34") (name "Net-(D14-A)") (class "Default")
      (node (ref "D14") (pin "2") (pinfunction "A_2") (pintype "unspecified"))
      (node (ref "SW14") (pin "1") (pinfunction "ROW_1") (pintype "input"))
    )
    (net (code "35") (name "Net-(D15-A)") (class "Default")
      (node (ref "D15") (pin "2") (pinfunction "A_2") (pintype "unspecified"))
      (node (ref "SW15") (pin "1") (pinfunction "ROW_1") (pintype "input"))
    )
    (net (code "36") (name "Net-(D16-A)") (class "Default")
      (node (ref "D16") (pin "2") (pinfunction "A_2") (pintype "unspecified"))
      (node (ref "SW16") (pin "1") (pinfunction "ROW_1") (pintype "input"))
    )
    (net (code "37") (name "Net-(D17-A)") (class "Default")
      (node (ref "D17") (pin "2") (pinfunction "A_2") (pintype "unspecified"))
      (node (ref "SW17") (pin "1") (pinfunction "ROW_1") (pintype "input"))
    )
    (net (code "38") (name "Net-(D18-K)") (class "Default")
      (node (ref "C2") (pin "1") (pinfunction "1_1") (pintype "unspecified"))
      (node (ref "D18") (pin "2") (pinfunction "K_2") (pintype "unspecified"))
      (node (ref "Q1") (pin "2") (pinfunction "S_2") (pintype "unspecified"))
      (node (ref "U1") (pin "3") (pinfunction "VIN_3") (pintype "unspecified"))
    )
    (net (code "39") (name "Net-(F1-Pad1)") (class "Default")
      (node (ref "F1") (pin "1") (pinfunction "1_1") (pintype "unspecified"))
      (node (ref "USB1") (pin "11") (pinfunction "VBUS_11") (pintype "unspecified"))
      (node (ref "USB1") (pin "2") (pinfunction "VBUS_2") (pintype "unspecified"))
    )
    (net (code "40") (name "Net-(H2-Pad1)") (class "Default")
      (node (ref "H2") (pin "1") (pinfunction "1_1") (pintype "unspecified"))
      (node (ref "SW18") (pin "2") (pinfunction "2_2") (pintype "unspecified"))
      (node (ref "SW18") (pin "3") (pinfunction "3_3") (pintype "unspecified"))
    )
    (net (code "41") (name "Net-(LED1-K)") (class "Default")
      (node (ref "LED1") (pin "1") (pinfunction "K_1") (pintype "input"))
      (node (ref "R5") (pin "1") (pinfunction "1_1") (pintype "unspecified"))
    )
    (net (code "42") (name "Net-(LED2-K)") (class "Default")
      (node (ref "LED2") (pin "1") (pinfunction "K_1") (pintype "input"))
      (node (ref "R6") (pin "1") (pinfunction "1_1") (pintype "unspecified"))
    )
    (net (code "43") (name "Net-(LED3-+)") (class "Default")
      (node (ref "LED3") (pin "2") (pinfunction "+_2") (pintype "input"))
      (node (ref "R7") (pin "1") (pinfunction "1_1") (pintype "input"))
    )
    (net (code "44") (name "Net-(U2-CHRG#)") (class "Default")
      (node (ref "R5") (pin "2") (pinfunction "2_2") (pintype "unspecified"))
      (node (ref "U2") (pin "1") (pinfunction "CHRG#_1") (pintype "unspecified"))
    )
    (net (code "45") (name "Net-(U2-PROG)") (class "Default")
      (node (ref "R4") (pin "1") (pinfunction "1_1") (pintype "input"))
      (node (ref "U2") (pin "6") (pinfunction "PROG_6") (pintype "unspecified"))
    )
    (net (code "46") (name "Net-(U2-STDBY#)") (class "Default")
      (node (ref "R6") (pin "2") (pinfunction "2_2") (pintype "unspecified"))
      (node (ref "U2") (pin "5") (pinfunction "STDBY#_5") (pintype "unspecified"))
    )
    (net (code "47") (name "Net-(U3-XL1)") (class "Default")
      (node (ref "U3") (pin "11") (pinfunction "XL1_11") (pintype "unspecified"))
      (node (ref "X1") (pin "1") (pinfunction "OSC1_1") (pintype "input"))
    )
    (net (code "48") (name "Net-(U3-XL2)") (class "Default")
      (node (ref "U3") (pin "13") (pinfunction "XL2_13") (pintype "unspecified"))
      (node (ref "X1") (pin "2") (pinfunction "OSC2_2") (pintype "input"))
    )
    (net (code "49") (name "Net-(USB1-CC1)") (class "Default")
      (node (ref "R2") (pin "1") (pinfunction "1_1") (pintype "input"))
      (node (ref "USB1") (pin "4") (pinfunction "CC1_4") (pintype "unspecified"))
    )
    (net (code "50") (name "Net-(USB1-CC2)") (class "Default")
      (node (ref "R1") (pin "1") (pinfunction "1_1") (pintype "input"))
      (node (ref "USB1") (pin "10") (pinfunction "CC2_10") (pintype "unspecified"))
    )
    (net (code "51") (name "unconnected-(U3-AI3-Pad15)") (class "Default")
      (node (ref "U3") (pin "15") (pinfunction "AI3_15") (pintype "unspecified+no_connect"))
    )
    (net (code "52") (name "unconnected-(U3-AI4-Pad4)") (class "Default")
      (node (ref "U3") (pin "4") (pinfunction "AI4_4") (pintype "unspecified+no_connect"))
    )
    (net (code "53") (name "unconnected-(U3-DCH-Pad25)") (class "Default")
      (node (ref "U3") (pin "25") (pinfunction "DCH_25") (pintype "unspecified+no_connect"))
    )
    (net (code "54") (name "unconnected-(U3-P0.06-Pad14)") (class "Default")
      (node (ref "U3") (pin "14") (pinfunction "P0.06_14") (pintype "unspecified+no_connect"))
    )
    (net (code "55") (name "unconnected-(U3-P0.07-Pad22)") (class "Default")
      (node (ref "U3") (pin "22") (pinfunction "P0.07_22") (pintype "unspecified+no_connect"))
    )
    (net (code "56") (name "unconnected-(U3-P0.08-Pad16)") (class "Default")
      (node (ref "U3") (pin "16") (pinfunction "P0.08_16") (pintype "unspecified+no_connect"))
    )
    (net (code "57") (name "unconnected-(U3-P0.20-Pad32)") (class "Default")
      (node (ref "U3") (pin "32") (pinfunction "P0.20_32") (pintype "unspecified+no_connect"))
    )
    (net (code "58") (name "unconnected-(U3-P0.22-Pad34)") (class "Default")
      (node (ref "U3") (pin "34") (pinfunction "P0.22_34") (pintype "unspecified+no_connect"))
    )
    (net (code "59") (name "unconnected-(U3-P0.24-Pad35)") (class "Default")
      (node (ref "U3") (pin "35") (pinfunction "P0.24_35") (pintype "unspecified+no_connect"))
    )
    (net (code "60") (name "unconnected-(U3-P0.26-Pad12)") (class "Default")
      (node (ref "U3") (pin "12") (pinfunction "P0.26_12") (pintype "unspecified+no_connect"))
    )
    (net (code "61") (name "unconnected-(U3-P1.00-Pad36)") (class "Default")
      (node (ref "U3") (pin "36") (pinfunction "P1.00_36") (pintype "unspecified+no_connect"))
    )
    (net (code "62") (name "unconnected-(U3-P1.02-Pad38)") (class "Default")
      (node (ref "U3") (pin "38") (pinfunction "P1.02_38") (pintype "unspecified+no_connect"))
    )
    (net (code "63") (name "unconnected-(U3-P1.04-Pad40)") (class "Default")
      (node (ref "U3") (pin "40") (pinfunction "P1.04_40") (pintype "unspecified+no_connect"))
    )
    (net (code "64") (name "unconnected-(U3-P1.06-Pad42)") (class "Default")
      (node (ref "U3") (pin "42") (pinfunction "P1.06_42") (pintype "unspecified+no_connect"))
    )
    (net (code "65") (name "unconnected-(U3-P1.09-Pad17)") (class "Default")
      (node (ref "U3") (pin "17") (pinfunction "P1.09_17") (pintype "unspecified+no_connect"))
    )
    (net (code "66") (name "unconnected-(U3-P1.11-Pad1)") (class "Default")
      (node (ref "U3") (pin "1") (pinfunction "P1.11_1") (pintype "unspecified+no_connect"))
    )
    (net (code "67") (name "unconnected-(U3-P12-Pad20)") (class "Default")
      (node (ref "U3") (pin "20") (pinfunction "P12_20") (pintype "unspecified+no_connect"))
    )
    (net (code "68") (name "unconnected-(U3-P15-Pad28)") (class "Default")
      (node (ref "U3") (pin "28") (pinfunction "P15_28") (pintype "unspecified+no_connect"))
    )
    (net (code "69") (name "unconnected-(U3-P17-Pad30)") (class "Default")
      (node (ref "U3") (pin "30") (pinfunction "P17_30") (pintype "unspecified+no_connect"))
    )
    (net (code "70") (name "unconnected-(USB1-SBU1-Pad9)") (class "Default")
      (node (ref "USB1") (pin "9") (pinfunction "SBU1_9") (pintype "unspecified+no_connect"))
    )
    (net (code "71") (name "unconnected-(USB1-SBU2-Pad3)") (class "Default")
      (node (ref "USB1") (pin "3") (pinfunction "SBU2_3") (pintype "unspecified+no_connect"))
    )
  )
)
